# REB215_XPRO_A_RF.net
KiCad netlist of a schematic drawn in Altium Designer
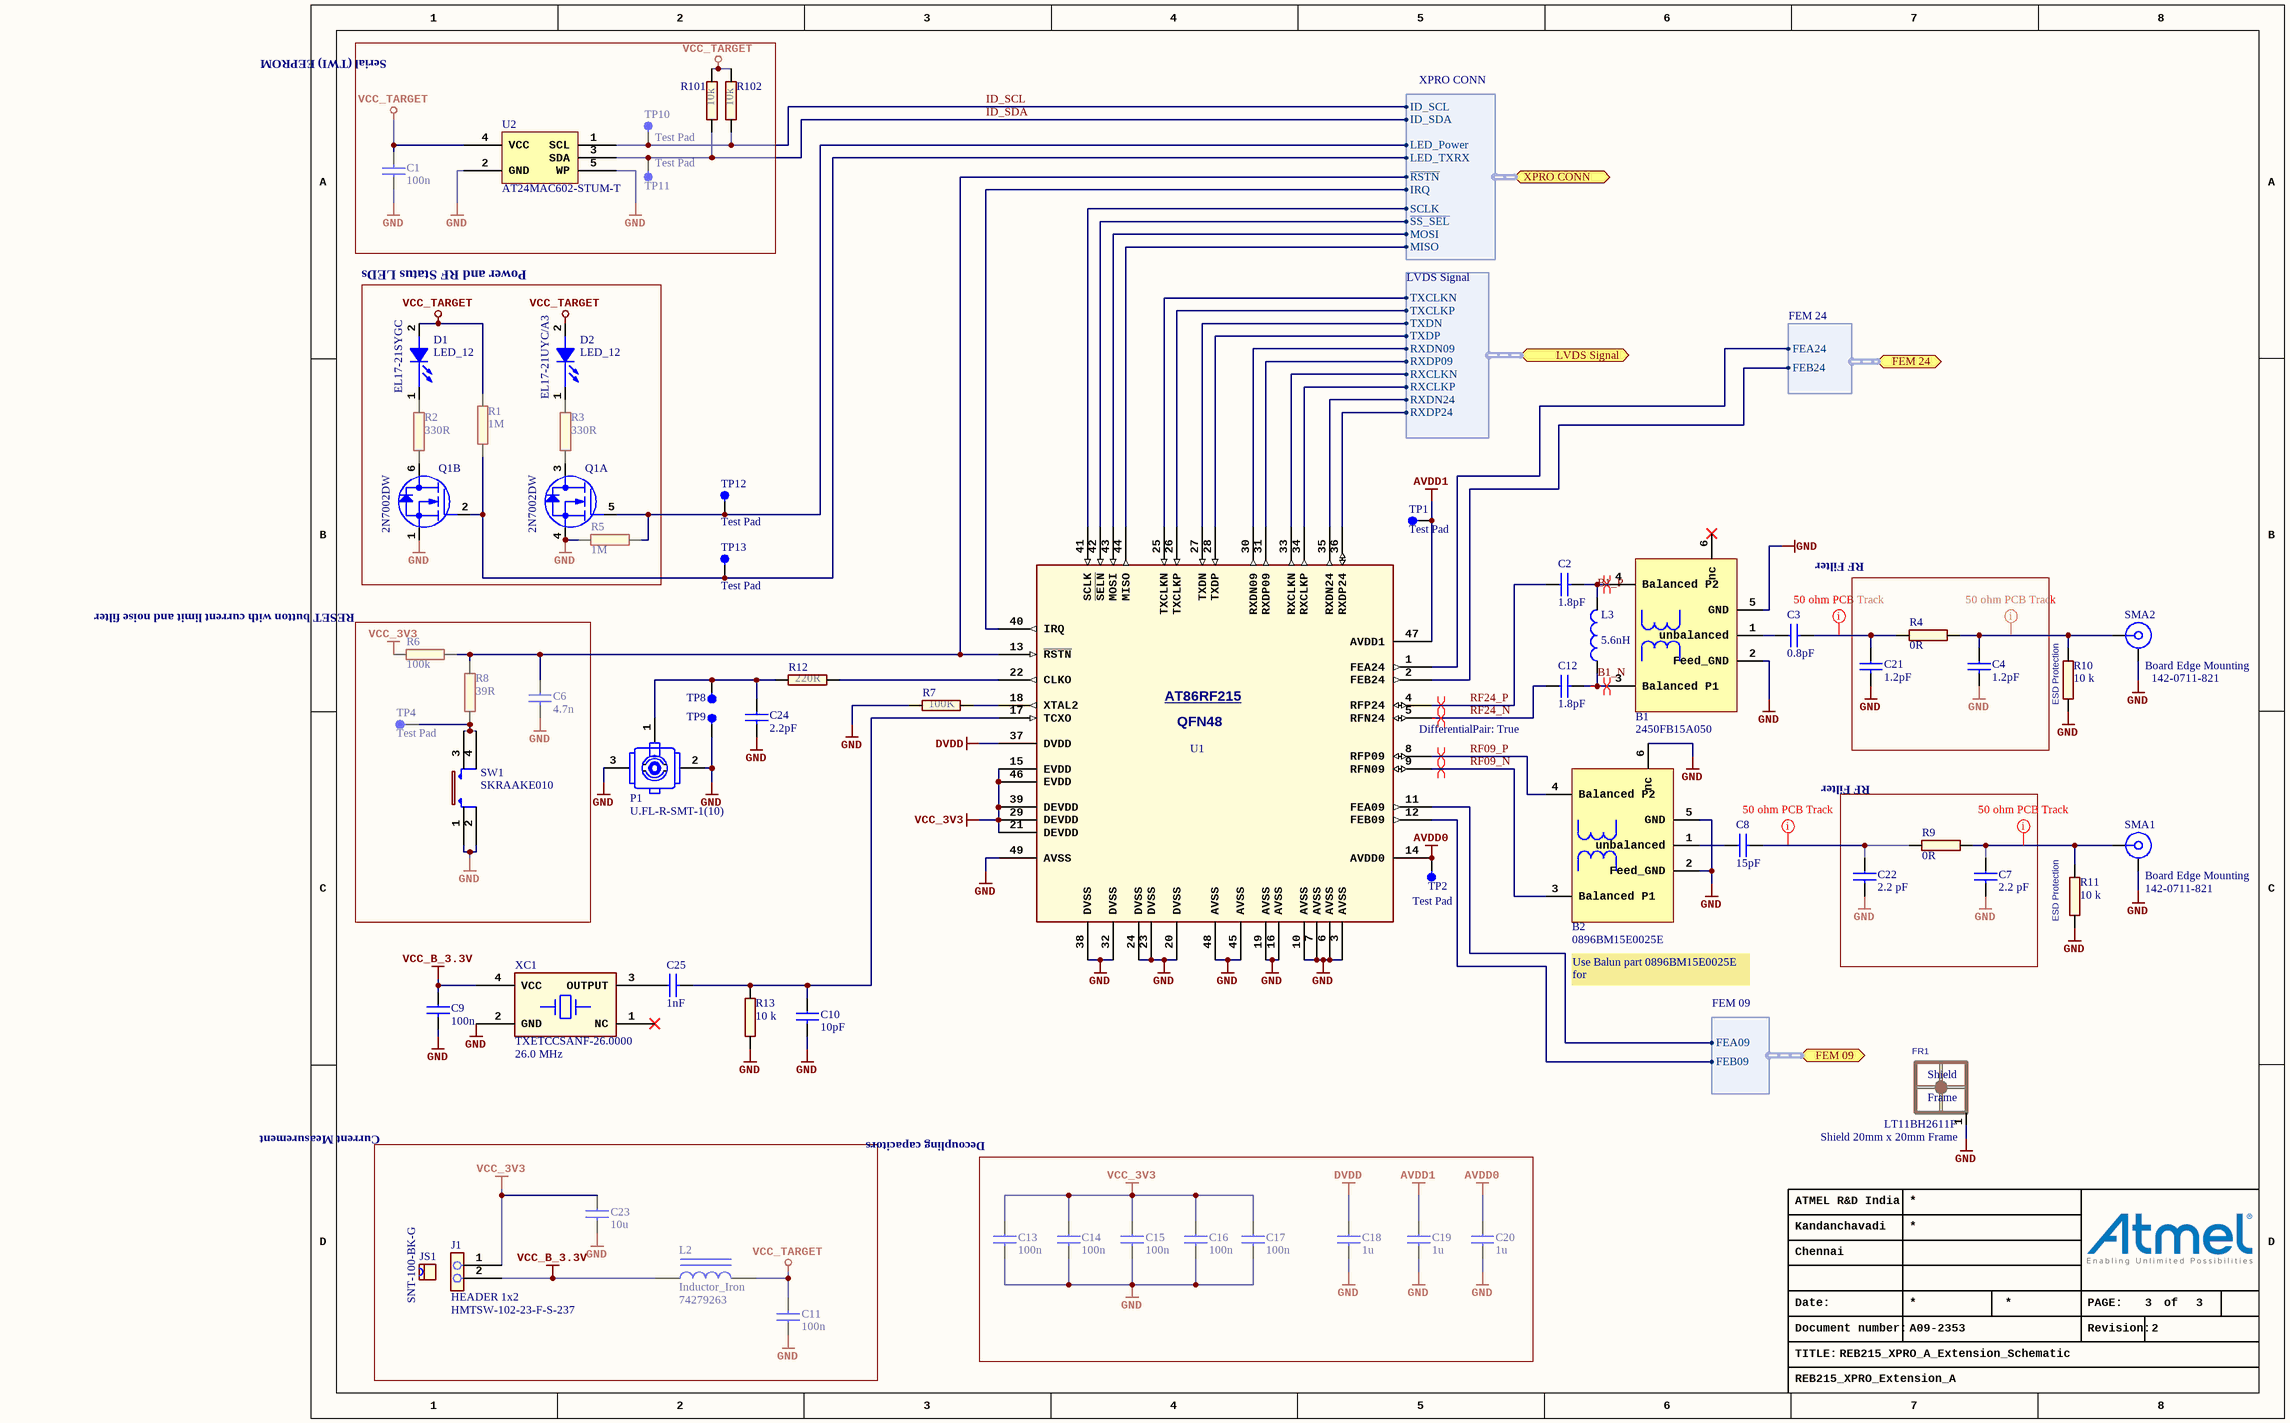
[diagram p0: REB215_XPRO_A_RF.SchDoc]

(export (version "E")
  (design (tool "Eeschema 10.0.6"))
  (components
    (comp (ref "B1")
      (value "2450FB15A050")
      (footprint "AP3-00060")
      (description "2.45 GHz Balun / Filter Combination")
      (fields (field (name "MANUFACTURER") "Johanson Technology") (field (name "Comment") "Balun_2.4GHz"))
      (libsource (lib "AltiumDbLib") (part "Balun_2.4GHz"))
    )
    (comp (ref "B2")
      (value "0896BM15E0025E")
      (footprint "AP3-00060")
      (description "863/915 MHz ISM band Balun+LPF for AT86RF215")
      (fields (field (name "MANUFACTURER") "Johanson Technology") (field (name "Comment") "Balun_2.4GHz"))
      (libsource (lib "AltiumDbLib") (part "Balun_2.4GHz"))
    )
    (comp (ref "C1")
      (value "100n")
      (footprint "AP1-00001")
      (description "Ceramic capacitor, SMD 0402, X7R, 16V, +/-10%")
      (fields
        (field (name "TOLERANCE") "16V, +/-10%")
        (field (name "MANUFACTURER") "Kemet")
        (field (name "VERIFIED BY") "Lars Helge Mo")
      )
      (libsource (lib "AltiumDbLib") (part "CAP-NONPOL"))
    )
    (comp (ref "C2")
      (value "1.8pF")
      (footprint "AP1-00035")
      (description "CAP CER 1.8PF 25V NP0 0201")
      (fields
        (field (name "TOLERANCE") "Â±0.1pF")
        (field (name "MANUFACTURER") "Johanson Technology")
        (field (name "VERIFIED BY") "Lars Helge Mo")
      )
      (libsource (lib "AltiumDbLib") (part "CAP-NONPOL"))
    )
    (comp (ref "C3")
      (value "0.8pF")
      (footprint "AP1-00035")
      (description "CAP CER 0.8PF 25V NP0 0201")
      (fields
        (field (name "TOLERANCE") "Â±0.05pF")
        (field (name "MANUFACTURER") "Johanson Technology")
        (field (name "VERIFIED BY") "Lars Helge Mo")
      )
      (libsource (lib "AltiumDbLib") (part "CAP-NONPOL"))
    )
    (comp (ref "C4")
      (value "1.2pF")
      (footprint "AP1-00035")
      (description "Ceramic Capacitor, SMD 0201, 25V, NP0, 1.2pF")
      (fields
        (field (name "MANUFACTURER") "Johanson Technology")
        (field (name "MPN") "250R05L1R2CV4T")
        (field (name "VERIFIED BY") "Lars Helge Mo")
      )
      (libsource (lib "AltiumDbLib") (part "CAP-NONPOL"))
    )
    (comp (ref "C6")
      (value "4.7n")
      (footprint "AP1-00001")
      (description "Ceramic capacitor, SMD 0402, X7R, 25V, +/-10% (de35287)")
      (fields
        (field (name "TOLERANCE") "25V, +/-10%")
        (field (name "Comment") "CAP-NONPOL")
        (field (name "VERIFIED BY") "Lars Helge Mo")
      )
      (libsource (lib "AltiumDbLib") (part "CAP-NONPOL"))
    )
    (comp (ref "C7")
      (value "2.2 pF")
      (footprint "AP1-00032")
      (description "CAP CER 2.2PF 6.3V NP0 0201")
      (fields
        (field (name "TOLERANCE") "±0.25pF")
        (field (name "MANUFACTURER") "Kemet")
        (field (name "VERIFIED BY") "Lars Helge Mo")
      )
      (libsource (lib "AltiumDbLib") (part "CAP-NONPOL"))
    )
    (comp (ref "C8")
      (value "15pF")
      (footprint "AP1-00032")
      (description "CAP CER 15PF 25V NP0 0201")
      (fields
        (field (name "TOLERANCE") "Â±5%")
        (field (name "MANUFACTURER") "Murata")
        (field (name "VERIFIED BY") "Lars Helge Mo")
      )
      (libsource (lib "AltiumDbLib") (part "CAP-NONPOL"))
    )
    (comp (ref "C9")
      (value "100n")
      (footprint "AP1-00001")
      (description "Ceramic capacitor, SMD 0402, X7R, 16V, +/-10%")
      (fields
        (field (name "TOLERANCE") "16V, +/-10%")
        (field (name "MANUFACTURER") "Kemet")
        (field (name "VERIFIED BY") "Lars Helge Mo")
      )
      (libsource (lib "AltiumDbLib") (part "CAP-NONPOL"))
    )
    (comp (ref "C10")
      (value "10pF")
      (footprint "AP1-00032")
      (description "CAP CER 10PF 25V Â±.25pf ( and Â±.30ppm/ degree C of temp variation) NP0 0201")
      (fields
        (field (name "TOLERANCE") "Â±20ppm to Â±50ppm")
        (field (name "MANUFACTURER") "tdk")
        (field (name "VERIFIED BY") "Lars Helge Mo")
      )
      (libsource (lib "AltiumDbLib") (part "CAP-NONPOL"))
    )
    (comp (ref "C11")
      (value "100n")
      (footprint "AP1-00001")
      (description "Ceramic capacitor, SMD 0402, X7R, 16V, +/-10%")
      (fields
        (field (name "TOLERANCE") "16V, +/-10%")
        (field (name "MANUFACTURER") "Kemet")
        (field (name "VERIFIED BY") "Lars Helge Mo")
      )
      (libsource (lib "AltiumDbLib") (part "CAP-NONPOL"))
    )
    (comp (ref "C12")
      (value "1.8pF")
      (footprint "AP1-00035")
      (description "CAP CER 1.8PF 25V NP0 0201")
      (fields
        (field (name "TOLERANCE") "Â±0.1pF")
        (field (name "MANUFACTURER") "Johanson Technology")
        (field (name "VERIFIED BY") "Lars Helge Mo")
      )
      (libsource (lib "AltiumDbLib") (part "CAP-NONPOL"))
    )
    (comp (ref "C13")
      (value "100n")
      (footprint "AP1-00001")
      (description "Ceramic capacitor, SMD 0402, X7R, 16V, +/-10%")
      (fields
        (field (name "TOLERANCE") "16V, +/-10%")
        (field (name "MANUFACTURER") "Kemet")
        (field (name "VERIFIED BY") "Lars Helge Mo")
      )
      (libsource (lib "AltiumDbLib") (part "CAP-NONPOL"))
    )
    (comp (ref "C14")
      (value "100n")
      (footprint "AP1-00001")
      (description "Ceramic capacitor, SMD 0402, X7R, 16V, +/-10%")
      (fields
        (field (name "TOLERANCE") "16V, +/-10%")
        (field (name "MANUFACTURER") "Kemet")
        (field (name "VERIFIED BY") "Lars Helge Mo")
      )
      (libsource (lib "AltiumDbLib") (part "CAP-NONPOL"))
    )
    (comp (ref "C15")
      (value "100n")
      (footprint "AP1-00001")
      (description "Ceramic capacitor, SMD 0402, X7R, 16V, +/-10%")
      (fields
        (field (name "TOLERANCE") "16V, +/-10%")
        (field (name "MANUFACTURER") "Kemet")
        (field (name "VERIFIED BY") "Lars Helge Mo")
      )
      (libsource (lib "AltiumDbLib") (part "CAP-NONPOL"))
    )
    (comp (ref "C16")
      (value "100n")
      (footprint "AP1-00001")
      (description "Ceramic capacitor, SMD 0402, X7R, 16V, +/-10%")
      (fields
        (field (name "TOLERANCE") "16V, +/-10%")
        (field (name "MANUFACTURER") "Kemet")
        (field (name "VERIFIED BY") "Lars Helge Mo")
      )
      (libsource (lib "AltiumDbLib") (part "CAP-NONPOL"))
    )
    (comp (ref "C17")
      (value "100n")
      (footprint "AP1-00001")
      (description "Ceramic capacitor, SMD 0402, X7R, 16V, +/-10%")
      (fields
        (field (name "TOLERANCE") "16V, +/-10%")
        (field (name "MANUFACTURER") "Kemet")
        (field (name "VERIFIED BY") "Lars Helge Mo")
      )
      (libsource (lib "AltiumDbLib") (part "CAP-NONPOL"))
    )
    (comp (ref "C18")
      (value "1u")
      (footprint "AP1-00001")
      (description "Ceramic capacitor, SMD 0402, X5R, 6.3V, +/-10% (de26942)")
      (fields
        (field (name "TOLERANCE") "+/-10%")
        (field (name "MANUFACTURER") "Kemet")
        (field (name "VERIFIED BY") "Lars Helge Mo")
      )
      (libsource (lib "AltiumDbLib") (part "CAP-NONPOL"))
    )
    (comp (ref "C19")
      (value "1u")
      (footprint "AP1-00001")
      (description "Ceramic capacitor, SMD 0402, X5R, 6.3V, +/-10% (de26942)")
      (fields
        (field (name "TOLERANCE") "+/-10%")
        (field (name "MANUFACTURER") "Kemet")
        (field (name "VERIFIED BY") "Lars Helge Mo")
      )
      (libsource (lib "AltiumDbLib") (part "CAP-NONPOL"))
    )
    (comp (ref "C20")
      (value "1u")
      (footprint "AP1-00001")
      (description "Ceramic capacitor, SMD 0402, X5R, 6.3V, +/-10% (de26942)")
      (fields
        (field (name "TOLERANCE") "+/-10%")
        (field (name "MANUFACTURER") "Kemet")
        (field (name "VERIFIED BY") "Lars Helge Mo")
      )
      (libsource (lib "AltiumDbLib") (part "CAP-NONPOL"))
    )
    (comp (ref "C21")
      (value "1.2pF")
      (footprint "AP1-00035")
      (description "Ceramic Capacitor, SMD 0201, 25V, NP0, 1.2pF")
      (fields
        (field (name "MANUFACTURER") "Johanson Technology")
        (field (name "MPN") "250R05L1R2CV4T")
        (field (name "VERIFIED BY") "Lars Helge Mo")
      )
      (libsource (lib "AltiumDbLib") (part "CAP-NONPOL"))
    )
    (comp (ref "C22")
      (value "2.2 pF")
      (footprint "AP1-00032")
      (description "CAP CER 2.2PF 6.3V NP0 0201")
      (fields
        (field (name "TOLERANCE") "±0.25pF")
        (field (name "MANUFACTURER") "Kemet")
        (field (name "VERIFIED BY") "Lars Helge Mo")
      )
      (libsource (lib "AltiumDbLib") (part "CAP-NONPOL"))
    )
    (comp (ref "C23")
      (value "10u")
      (footprint "AP1-00026")
      (description "Ceramic capacitor, SMD 1206, X5R, 6.3V, ±10%")
      (fields
        (field (name "TOLERANCE") "±10%")
        (field (name "MANUFACTURER") "Murata")
        (field (name "VERIFIED BY") "Lars Helge Mo")
      )
      (libsource (lib "AltiumDbLib") (part "CAP-NONPOL"))
    )
    (comp (ref "C24")
      (value "2.2pF")
      (footprint "AP1-00038")
      (description "Ceramic capacitor, SMD 0402, NP0, 50V, +/-0.25pF (de23847)")
      (fields
        (field (name "TOLERANCE") "0,25pF")
        (field (name "MANUFACTURER") "Murata")
        (field (name "VERIFIED BY") "Lars Helge Mo")
      )
      (libsource (lib "AltiumDbLib") (part "CAP-NONPOL"))
    )
    (comp (ref "C25")
      (value "1nF")
      (footprint "AP1-00035")
      (description "Ceramic capacitor, SMD 0201, X7R, 10V, +/-10%")
      (fields
        (field (name "MANUFACTURER") "Johanson Technology")
        (field (name "MPN") "100R05W102KV4")
        (field (name "VERIFIED BY") "Lars Helge Mo")
      )
      (libsource (lib "AltiumDbLib") (part "CAP-NONPOL"))
    )
    (comp (ref "D1")
      (value "LED_12")
      (footprint "AP4-00013")
      (description "LED, Green, Wave length=575nm, SMD 0805, ±70°")
      (fields
        (field (name "ALTIUM_VALUE") "EL17-21SYGC")
        (field (name "MANUFACTURER") "Everlight")
        (field (name "MPN") "EL17-21SYGC")
        (field (name "VERIFIED BY") "Sveinung Helgeland")
      )
      (libsource (lib "AltiumDbLib") (part "LED_12"))
    )
    (comp (ref "D2")
      (value "LED_12")
      (footprint "AP4-00013")
      (description "LED, Yellow, Wave length=591nm, SMD 0805, ±70°")
      (fields
        (field (name "ALTIUM_VALUE") "EL17-21UYC/A3")
        (field (name "MANUFACTURER") "Everlight")
        (field (name "MPN") "17-21UYC/S530-A3/TR8")
        (field (name "VERIFIED BY") "Sveinung Helgeland")
      )
      (libsource (lib "AltiumDbLib") (part "LED_12"))
    )
    (comp (ref "FR1")
      (value "Shield 20mm x 20mm Frame")
      (footprint "AP8-00753")
      (description "SMD frame for metal shield 20mm x 20mm (de34031)")
      (fields
        (field (name "ALTIUM_VALUE") "LT11BH2611F")
        (field (name "MANUFACTURER") "Laird Technologies")
        (field (name "MPN") "LT11BH2611F")
      )
      (libsource (lib "AltiumDbLib") (part "FRAME20X20MM"))
    )
    (comp (ref "J1")
      (value "HEADER 1x2")
      (footprint "AP8-00733")
      (description "1x2 pin header, 2.54mm pitch, Pin-in-Paste THM")
      (fields
        (field (name "ALTIUM_VALUE") "HMTSW-102-23-F-S-237")
        (field (name "MANUFACTURER") "SAMTEC")
        (field (name "MPN") "HMTSW-102-23-F-S-237")
        (field (name "VERIFIED BY") "Lars Helge")
      )
      (libsource (lib "AltiumDbLib") (part "HEADER 1x2"))
    )
    (comp (ref "JS1")
      (value "SNT-100-BK-G")
      (footprint "AP8-00525")
      (description "Jumper cap for 2.54mm pinheader")
      (fields
        (field (name "MANUFACTURER") "SAMTEC")
        (field (name "Comment") "To be used by request from ESCATEC")
        (field (name "VERIFIED BY") "Lars Helge Mo")
      )
      (libsource (lib "AltiumDbLib") (part "JUMPER_CAP"))
    )
    (comp (ref "L2")
      (value "Inductor_Iron")
      (footprint "AP3-00049")
      (description "SMD-Ferrite 220Ohm, 100MHz 0603 size, (de14411)")
      (fields
        (field (name "ALTIUM_VALUE") "74279263")
        (field (name "MANUFACTURER") "Wurth Elektronik")
        (field (name "MPN") "74279263")
      )
      (libsource (lib "AltiumDbLib") (part "Inductor_Iron"))
    )
    (comp (ref "L3")
      (value "5.6nH")
      (footprint "AP3-00041")
      (description "ceramic chip inductor, 5.6nH, 0201")
      (fields
        (field (name "TOLERANCE") "±0.3nH")
        (field (name "MANUFACTURER") "Johanson Technology")
        (field (name "VERIFIED BY") "Lars Helge Mo")
      )
      (libsource (lib "AltiumDbLib") (part "INDUCTOR"))
    )
    (comp (ref "P1")
      (value "U.FL-R-SMT-1(10)")
      (footprint "AP8-00380")
      (description "UFL (Small Coax Connector)")
      (fields (field (name "MANUFACTURER") "HIROSE") (field (name "Comment") "Copy of A08-0629"))
      (libsource (lib "AltiumDbLib") (part "U.FL-R-SMT"))
    )
    (comp (ref "Q1")
      (value "2N7002DW")
      (footprint "AP5-00001")
      (description "Dual N-Channel MOSFET, 60V, 115mA cont,RDS(ON) < 7.5 Ohm @50mA@5V, SOT-363")
      (fields
        (field (name "MANUFACTURER") "Fairchild")
        (field (name "Comment") "Same as 2N7002 but with two MOSFETs in one package")
      )
      (libsource (lib "AltiumDbLib") (part "MOSFET_DUAL_N_S2G2D1S1G1D2"))
    )
    (comp (ref "R1")
      (value "1M")
      (footprint "AP2-00000")
      (description "Thick film resistor, SMD 0402, 1/16W, 1%")
      (fields
        (field (name "TOLERANCE") "1 %")
        (field (name "Comment") "R2")
        (field (name "VERIFIED BY") "Lars Helge Mo")
      )
      (libsource (lib "") (part "R2_1"))
    )
    (comp (ref "R2")
      (value "330R")
      (footprint "AP2-00000")
      (description "Thick film resistor, SMD 0402, 1/16W, 1%")
      (fields
        (field (name "TOLERANCE") "1 %")
        (field (name "Comment") "R2")
        (field (name "VERIFIED BY") "Lars Helge Mo")
      )
      (libsource (lib "") (part "R2_1"))
    )
    (comp (ref "R3")
      (value "330R")
      (footprint "AP2-00000")
      (description "Thick film resistor, SMD 0402, 1/16W, 1%")
      (fields
        (field (name "TOLERANCE") "1 %")
        (field (name "Comment") "R2")
        (field (name "VERIFIED BY") "Lars Helge Mo")
      )
      (libsource (lib "") (part "R2_1"))
    )
    (comp (ref "R4")
      (value "0R")
      (footprint "AP2-00028")
      (description "Thick film resistor, SMD 0201, 1/20W, 5%")
      (fields
        (field (name "TOLERANCE") "5%")
        (field (name "MANUFACTURER") "ROHM")
        (field (name "VERIFIED BY") "Lars Helge Mo")
      )
      (libsource (lib "") (part "R2_2"))
    )
    (comp (ref "R5")
      (value "1M")
      (footprint "AP2-00000")
      (description "Thick film resistor, SMD 0402, 1/16W, 1%")
      (fields
        (field (name "TOLERANCE") "1 %")
        (field (name "Comment") "R2")
        (field (name "VERIFIED BY") "Lars Helge Mo")
      )
      (libsource (lib "AltiumDbLib") (part "R2"))
    )
    (comp (ref "R6")
      (value "100k")
      (footprint "AP2-00000")
      (description "Thick film resistor, SMD 0402, 1/16W, 1%")
      (fields
        (field (name "TOLERANCE") "1 %")
        (field (name "Comment") "R2")
        (field (name "VERIFIED BY") "Lars Helge Mo")
      )
      (libsource (lib "AltiumDbLib") (part "R2"))
    )
    (comp (ref "R7")
      (value "100K")
      (footprint "AP2-00028")
      (description "RES 100K OHM 1/20W 5% 0201 SMD")
      (fields
        (field (name "MANUFACTURER") "YAGEO CORP")
        (field (name "MPN") "RC0201JR-07100KL")
        (field (name "VERIFIED BY") "Lars Helge Mo")
      )
      (libsource (lib "AltiumDbLib") (part "R2"))
    )
    (comp (ref "R8")
      (value "39R")
      (footprint "AP2-00000")
      (description "Thick film resistor, SMD 0402, 1/16W, 1%")
      (fields
        (field (name "TOLERANCE") "1 %")
        (field (name "Comment") "R2")
        (field (name "VERIFIED BY") "Lars Helge Mo")
      )
      (libsource (lib "") (part "R2_1"))
    )
    (comp (ref "R9")
      (value "0R")
      (footprint "AP2-00028")
      (description "Thick film resistor, SMD 0201, 1/20W, 5%")
      (fields
        (field (name "TOLERANCE") "5%")
        (field (name "MANUFACTURER") "ROHM")
        (field (name "VERIFIED BY") "Lars Helge Mo")
      )
      (libsource (lib "") (part "R2_2"))
    )
    (comp (ref "R10")
      (value "10 k")
      (footprint "AP2-00028")
      (description "Thick film resistor, SMD 0201, 1/20W, 5%")
      (fields
        (field (name "TOLERANCE") "5%")
        (field (name "MANUFACTURER") "ROHM")
        (field (name "VERIFIED BY") "Lars Helge Mo")
      )
      (libsource (lib "") (part "R2_1"))
    )
    (comp (ref "R11")
      (value "10 k")
      (footprint "AP2-00028")
      (description "Thick film resistor, SMD 0201, 1/20W, 5%")
      (fields
        (field (name "TOLERANCE") "5%")
        (field (name "MANUFACTURER") "ROHM")
        (field (name "VERIFIED BY") "Lars Helge Mo")
      )
      (libsource (lib "") (part "R2_1"))
    )
    (comp (ref "R12")
      (value "220R")
      (footprint "AP2-00000")
      (description "Thick film resistor, SMD 0402, 1/16W, 1%")
      (fields
        (field (name "TOLERANCE") "1 %")
        (field (name "Comment") "R2")
        (field (name "VERIFIED BY") "Lars Helge Mo")
      )
      (libsource (lib "") (part "R2_2"))
    )
    (comp (ref "R13")
      (value "10 k")
      (footprint "AP2-00028")
      (description "Thick film resistor, SMD 0201, 1/20W, 5%")
      (fields
        (field (name "TOLERANCE") "5%")
        (field (name "MANUFACTURER") "ROHM")
        (field (name "VERIFIED BY") "Lars Helge Mo")
      )
      (libsource (lib "") (part "R2_1"))
    )
    (comp (ref "R101")
      (value "10k")
      (footprint "AP2-00000")
      (description "Thick film resistor, SMD 0402, 1/16W, 1%")
      (fields
        (field (name "TOLERANCE") "1 %")
        (field (name "MANUFACTURER") "vishay")
        (field (name "VERIFIED BY") "Lars Helge Mo")
      )
      (libsource (lib "") (part "R2_1"))
    )
    (comp (ref "R102")
      (value "10k")
      (footprint "AP2-00000")
      (description "Thick film resistor, SMD 0402, 1/16W, 1%")
      (fields
        (field (name "TOLERANCE") "1 %")
        (field (name "MANUFACTURER") "vishay")
        (field (name "VERIFIED BY") "Lars Helge Mo")
      )
      (libsource (lib "") (part "R2_1"))
    )
    (comp (ref "SMA1")
      (value "Board Edge Mounting")
      (footprint "AP8-00443")
      (description "End Launch Jack Receptacle, Round Contact (de21535)")
      (fields
        (field (name "ALTIUM_VALUE") "142-0711-821")
        (field (name "MANUFACTURER") "EMERSON")
        (field (name "MPN") "142-0711-821")
      )
      (libsource (lib "AltiumDbLib") (part "SMA_3_pin"))
    )
    (comp (ref "SMA2")
      (value "Board Edge Mounting")
      (footprint "AP8-00443")
      (description "End Launch Jack Receptacle, Round Contact (de21535)")
      (fields
        (field (name "ALTIUM_VALUE") "142-0711-821")
        (field (name "MANUFACTURER") "EMERSON")
        (field (name "MPN") "142-0711-821")
      )
      (libsource (lib "AltiumDbLib") (part "SMA_3_pin"))
    )
    (comp (ref "SW1")
      (value "SKRAAKE010")
      (footprint "AP8-00137")
      (description "SWITCH, SMD, 2.45N, 6.2mm X 6.2mm")
      (fields
        (field (name "MANUFACTURER") "ALPS")
        (field (name "Comment") "same as A08-0091 but less force is needed; Can be ordered in low volumes from Mouser")
        (field (name "VERIFIED BY") "Ketil Skjerve")
      )
      (libsource (lib "AltiumDbLib") (part "PUSHBUTTON1"))
    )
    (comp (ref "TP1")
      (value "Test Pad")
      (footprint "AP8-00399")
      (description "Single SMD testpad")
      (fields (field (name "Comment") "TESTPOINT") (field (name "VERIFIED BY") "Sveinung Helgeland"))
      (libsource (lib "AltiumDbLib") (part "TESTPOINT"))
    )
    (comp (ref "TP2")
      (value "Test Pad")
      (footprint "AP8-00399")
      (description "Single SMD testpad")
      (fields (field (name "Comment") "TESTPOINT") (field (name "VERIFIED BY") "Sveinung Helgeland"))
      (libsource (lib "AltiumDbLib") (part "TESTPOINT"))
    )
    (comp (ref "TP4")
      (value "Test Pad")
      (footprint "AP8-00399")
      (description "Single SMD testpad")
      (fields (field (name "Comment") "TESTPOINT") (field (name "VERIFIED BY") "Sveinung Helgeland"))
      (libsource (lib "AltiumDbLib") (part "TESTPOINT"))
    )
    (comp (ref "TP8")
      (value "Mounting hole dia should be 1.6mm. Refer A08-2059")
      (footprint "AP8-00710")
      (description "THM Test Point, Without Base, 1.0mm Dia. Mounting")
      (fields
        (field (name "MANUFACTURER") "Keystone Corp.")
        (field (name "MPN") "5012")
        (field (name "VERIFIED BY") "Sveinung Helgeland")
      )
      (libsource (lib "AltiumDbLib") (part "TESTPOINT"))
    )
    (comp (ref "TP9")
      (value "Mounting hole dia should be 1.6mm. Refer A08-2059")
      (footprint "AP8-00710")
      (description "THM Test Point, Without Base, 1.0mm Dia. Mounting")
      (fields
        (field (name "MANUFACTURER") "Keystone Corp.")
        (field (name "MPN") "5012")
        (field (name "VERIFIED BY") "Sveinung Helgeland")
      )
      (libsource (lib "AltiumDbLib") (part "TESTPOINT"))
    )
    (comp (ref "TP10")
      (value "Test Pad")
      (footprint "AP8-00399")
      (description "Single SMD testpad")
      (fields (field (name "Comment") "TESTPOINT") (field (name "VERIFIED BY") "Sveinung Helgeland"))
      (libsource (lib "AltiumDbLib") (part "TESTPOINT"))
    )
    (comp (ref "TP11")
      (value "Test Pad")
      (footprint "AP8-00399")
      (description "Single SMD testpad")
      (fields (field (name "Comment") "TESTPOINT") (field (name "VERIFIED BY") "Sveinung Helgeland"))
      (libsource (lib "AltiumDbLib") (part "TESTPOINT"))
    )
    (comp (ref "TP12")
      (value "Test Pad")
      (footprint "AP8-00399")
      (description "Single SMD testpad")
      (fields (field (name "Comment") "TESTPOINT") (field (name "VERIFIED BY") "Sveinung Helgeland"))
      (libsource (lib "AltiumDbLib") (part "TESTPOINT"))
    )
    (comp (ref "TP13")
      (value "Test Pad")
      (footprint "AP8-00399")
      (description "Single SMD testpad")
      (fields (field (name "Comment") "TESTPOINT") (field (name "VERIFIED BY") "Sveinung Helgeland"))
      (libsource (lib "AltiumDbLib") (part "TESTPOINT"))
    )
    (comp (ref "U1")
      (value "48 lead QFN package")
      (footprint "AP6-00345")
      (description "Sub-1GHz/2.4GHz Transceiver")
      (fields (field (name "MANUFACTURER") "ATMEL") (field (name "MPN") "AT86RF215-ZU"))
      (libsource (lib "AltiumDbLib") (part "AT86RF215"))
    )
    (comp (ref "U2")
      (value "AT24MAC602-STUM-T")
      (footprint "AP6-00014")
      (description "IC EEPROM 2KBIT 1MHz, 1.7V to 5.5V, SOT23-5")
      (fields
        (field (name "MANUFACTURER") "ATMEL")
        (field (name "Comment") "AT24MAC602")
        (field (name "VERIFIED BY") "*")
      )
      (libsource (lib "AltiumDbLib") (part "AT24MAC602"))
    )
    (comp (ref "XC1")
      (value "TXETCCSANF-26.0000")
      (footprint "AP7-00060")
      (description "26MHz TCXO, 2.8 ~ 3.3V, Clipped sine wave 10KOhm/10pF, 3.2 x 2.5 mm SMD")
      (fields
        (field (name "ALTIUM_VALUE") "26.0 MHz")
        (field (name "TOLERANCE") "+/-2ppm")
        (field (name "MANUFACTURER") "Taiway Electronics")
      )
      (libsource (lib "AltiumDbLib") (part "ACT33T-4 TCXO"))
    )
  )
  (nets
    (net (code "8") (name "/B1_N") (class "Default")
      (node (ref "B1") (pin "3") (pinfunction "Balanced_P1_3") (pintype "passive"))
      (node (ref "C12") (pin "2") (pinfunction "2_2") (pintype "passive"))
      (node (ref "L3") (pin "1") (pinfunction "1_1") (pintype "passive"))
    )
    (net (code "9") (name "/B1_P") (class "Default")
      (node (ref "B1") (pin "4") (pinfunction "Balanced_P2_4") (pintype "passive"))
      (node (ref "C2") (pin "2") (pinfunction "2_2") (pintype "passive"))
      (node (ref "L3") (pin "2") (pinfunction "2_2") (pintype "passive"))
    )
    (net (code "10") (name "/FEA09") (class "Default")
      (node (ref "U1") (pin "11") (pinfunction "FEA09_11") (pintype "output"))
    )
    (net (code "11") (name "/FEA24") (class "Default")
      (node (ref "U1") (pin "1") (pinfunction "FEA24_1") (pintype "output"))
    )
    (net (code "12") (name "/FEB09") (class "Default")
      (node (ref "U1") (pin "12") (pinfunction "FEB09_12") (pintype "output"))
    )
    (net (code "13") (name "/FEB24") (class "Default")
      (node (ref "U1") (pin "2") (pinfunction "FEB24_2") (pintype "output"))
    )
    (net (code "14") (name "/ID_SCL") (class "Default")
      (node (ref "R102") (pin "1") (pinfunction "1_1") (pintype "passive"))
      (node (ref "TP10") (pin "1") (pinfunction "1_1") (pintype "passive"))
      (node (ref "U2") (pin "1") (pinfunction "SCL_1") (pintype "passive"))
    )
    (net (code "15") (name "/ID_SDA") (class "Default")
      (node (ref "R101") (pin "1") (pinfunction "1_1") (pintype "passive"))
      (node (ref "TP11") (pin "1") (pinfunction "1_1") (pintype "passive"))
      (node (ref "U2") (pin "3") (pinfunction "SDA_3") (pintype "passive"))
    )
    (net (code "16") (name "/IRQ") (class "Default")
      (node (ref "U1") (pin "40") (pinfunction "IRQ_40") (pintype "output"))
    )
    (net (code "17") (name "/LED_Power") (class "Default")
      (node (ref "Q1") (pin "5") (pinfunction "G1_5") (pintype "passive"))
      (node (ref "R5") (pin "1") (pinfunction "1_1") (pintype "passive"))
      (node (ref "TP12") (pin "1") (pinfunction "1_1") (pintype "passive"))
    )
    (net (code "18") (name "/LED_TXRX") (class "Default")
      (node (ref "Q1") (pin "2") (pinfunction "G2_2") (pintype "passive"))
      (node (ref "R1") (pin "1") (pinfunction "1_1") (pintype "passive"))
      (node (ref "TP13") (pin "1") (pinfunction "1_1") (pintype "passive"))
    )
    (net (code "19") (name "/MISO") (class "Default")
      (node (ref "U1") (pin "44") (pinfunction "MISO_44") (pintype "output"))
    )
    (net (code "20") (name "/MOSI") (class "Default")
      (node (ref "U1") (pin "43") (pinfunction "MOSI_43") (pintype "input"))
    )
    (net (code "21") (name "/RF09_N") (class "Default")
      (node (ref "B2") (pin "3") (pinfunction "Balanced_P1_3") (pintype "passive"))
      (node (ref "U1") (pin "9") (pinfunction "RFN09_9") (pintype "bidirectional"))
    )
    (net (code "22") (name "/RF09_P") (class "Default")
      (node (ref "B2") (pin "4") (pinfunction "Balanced_P2_4") (pintype "passive"))
      (node (ref "U1") (pin "8") (pinfunction "RFP09_8") (pintype "bidirectional"))
    )
    (net (code "23") (name "/RF24_N") (class "Default")
      (node (ref "C12") (pin "1") (pinfunction "1_1") (pintype "passive"))
      (node (ref "U1") (pin "5") (pinfunction "RFN24_5") (pintype "bidirectional"))
    )
    (net (code "24") (name "/RF24_P") (class "Default")
      (node (ref "C2") (pin "1") (pinfunction "1_1") (pintype "passive"))
      (node (ref "U1") (pin "4") (pinfunction "RFP24_4") (pintype "bidirectional"))
    )
    (net (code "25") (name "/RXCLKN") (class "Default")
      (node (ref "U1") (pin "33") (pinfunction "RXCLKN_33") (pintype "output"))
    )
    (net (code "26") (name "/RXCLKP") (class "Default")
      (node (ref "U1") (pin "34") (pinfunction "RXCLKP_34") (pintype "output"))
    )
    (net (code "27") (name "/RXDN09") (class "Default")
      (node (ref "U1") (pin "30") (pinfunction "RXDN09_30") (pintype "output"))
    )
    (net (code "28") (name "/RXDN24") (class "Default")
      (node (ref "U1") (pin "35") (pinfunction "RXDN24_35") (pintype "output"))
    )
    (net (code "29") (name "/RXDP09") (class "Default")
      (node (ref "U1") (pin "31") (pinfunction "RXDP09_31") (pintype "output"))
    )
    (net (code "30") (name "/RXDP24") (class "Default")
      (node (ref "U1") (pin "36") (pinfunction "RXDP24_36") (pintype "bidirectional"))
    )
    (net (code "31") (name "/SCLK") (class "Default")
      (node (ref "U1") (pin "41") (pinfunction "SCLK_41") (pintype "input"))
    )
    (net (code "32") (name "/TXCLKN") (class "Default")
      (node (ref "U1") (pin "25") (pinfunction "TXCLKN_25") (pintype "input"))
    )
    (net (code "33") (name "/TXCLKP") (class "Default")
      (node (ref "U1") (pin "26") (pinfunction "TXCLKP_26") (pintype "input"))
    )
    (net (code "34") (name "/TXDN") (class "Default")
      (node (ref "U1") (pin "27") (pinfunction "TXDN_27") (pintype "input"))
    )
    (net (code "35") (name "/TXDP") (class "Default")
      (node (ref "U1") (pin "28") (pinfunction "TXDP_28") (pintype "input"))
    )
    (net (code "40") (name "/~{RSTN}") (class "Default")
      (node (ref "C6") (pin "1") (pinfunction "1_1") (pintype "passive"))
      (node (ref "R6") (pin "1") (pinfunction "1_1") (pintype "passive"))
      (node (ref "R8") (pin "2") (pinfunction "2_2") (pintype "passive"))
      (node (ref "U1") (pin "13") (pinfunction "~{RSTN}_13") (pintype "input"))
    )
    (net (code "41") (name "/~{SS_SEL}") (class "Default")
      (node (ref "U1") (pin "42") (pinfunction "~{SELN}_42") (pintype "input"))
    )
    (net (code "42") (name "AVDD0") (class "Default")
      (node (ref "C20") (pin "1") (pinfunction "1_1") (pintype "passive"))
      (node (ref "TP2") (pin "1") (pinfunction "1_1") (pintype "passive"))
      (node (ref "U1") (pin "14") (pinfunction "AVDD0_14") (pintype "power_in"))
    )
    (net (code "43") (name "AVDD1") (class "Default")
      (node (ref "C19") (pin "1") (pinfunction "1_1") (pintype "passive"))
      (node (ref "TP1") (pin "1") (pinfunction "1_1") (pintype "passive"))
      (node (ref "U1") (pin "47") (pinfunction "AVDD1_47") (pintype "power_in"))
    )
    (net (code "44") (name "DVDD") (class "Default")
      (node (ref "C18") (pin "1") (pinfunction "1_1") (pintype "passive"))
      (node (ref "U1") (pin "37") (pinfunction "DVDD_37") (pintype "power_in"))
    )
    (net (code "45") (name "GND") (class "Default")
      (node (ref "B1") (pin "2") (pinfunction "Feed_GND_2") (pintype "power_in"))
      (node (ref "B1") (pin "5") (pinfunction "GND_5") (pintype "power_in"))
      (node (ref "B2") (pin "2") (pinfunction "Feed_GND_2") (pintype "power_in"))
      (node (ref "B2") (pin "5") (pinfunction "GND_5") (pintype "power_in"))
      (node (ref "B2") (pin "6") (pinfunction "nc_6") (pintype "passive"))
      (node (ref "C1") (pin "1") (pinfunction "1_1") (pintype "passive"))
      (node (ref "C10") (pin "2") (pinfunction "2_2") (pintype "passive"))
      (node (ref "C11") (pin "1") (pinfunction "1_1") (pintype "passive"))
      (node (ref "C13") (pin "2") (pinfunction "2_2") (pintype "passive"))
      (node (ref "C14") (pin "2") (pinfunction "2_2") (pintype "passive"))
      (node (ref "C15") (pin "2") (pinfunction "2_2") (pintype "passive"))
      (node (ref "C16") (pin "2") (pinfunction "2_2") (pintype "passive"))
      (node (ref "C17") (pin "2") (pinfunction "2_2") (pintype "passive"))
      (node (ref "C18") (pin "2") (pinfunction "2_2") (pintype "passive"))
      (node (ref "C19") (pin "2") (pinfunction "2_2") (pintype "passive"))
      (node (ref "C20") (pin "2") (pinfunction "2_2") (pintype "passive"))
      (node (ref "C21") (pin "2") (pinfunction "2_2") (pintype "passive"))
      (node (ref "C22") (pin "2") (pinfunction "2_2") (pintype "passive"))
      (node (ref "C23") (pin "2") (pinfunction "2_2") (pintype "passive"))
      (node (ref "C24") (pin "2") (pinfunction "2_2") (pintype "passive"))
      (node (ref "C4") (pin "2") (pinfunction "2_2") (pintype "passive"))
      (node (ref "C6") (pin "2") (pinfunction "2_2") (pintype "passive"))
      (node (ref "C7") (pin "2") (pinfunction "2_2") (pintype "passive"))
      (node (ref "C9") (pin "2") (pinfunction "2_2") (pintype "passive"))
      (node (ref "FR1") (pin "1") (pinfunction "GND_1") (pintype "passive"))
      (node (ref "P1") (pin "2") (pinfunction "GND_2") (pintype "power_in"))
      (node (ref "P1") (pin "3") (pinfunction "GND_3") (pintype "power_in"))
      (node (ref "Q1") (pin "1") (pinfunction "S2_1") (pintype "passive"))
      (node (ref "Q1") (pin "4") (pinfunction "S1_4") (pintype "passive"))
      (node (ref "R10") (pin "1") (pinfunction "1_1") (pintype "passive"))
      (node (ref "R11") (pin "1") (pinfunction "1_1") (pintype "passive"))
      (node (ref "R13") (pin "1") (pinfunction "1_1") (pintype "passive"))
      (node (ref "R5") (pin "2") (pinfunction "2_2") (pintype "passive"))
      (node (ref "R7") (pin "2") (pinfunction "2_2") (pintype "passive"))
      (node (ref "SMA1") (pin "2") (pinfunction "2_2") (pintype "passive"))
      (node (ref "SMA2") (pin "2") (pinfunction "2_2") (pintype "passive"))
      (node (ref "SW1") (pin "1") (pinfunction "1_1") (pintype "passive"))
      (node (ref "SW1") (pin "2") (pinfunction "2_2") (pintype "passive"))
      (node (ref "TP9") (pin "1") (pinfunction "1_1") (pintype "passive"))
      (node (ref "U1") (pin "10") (pinfunction "AVSS_10") (pintype "power_in"))
      (node (ref "U1") (pin "16") (pinfunction "AVSS_16") (pintype "power_in"))
      (node (ref "U1") (pin "19") (pinfunction "AVSS_19") (pintype "power_in"))
      (node (ref "U1") (pin "20") (pinfunction "DVSS_20") (pintype "power_in"))
      (node (ref "U1") (pin "23") (pinfunction "DVSS_23") (pintype "power_in"))
      (node (ref "U1") (pin "24") (pinfunction "DVSS_24") (pintype "power_in"))
      (node (ref "U1") (pin "3") (pinfunction "AVSS_3") (pintype "power_in"))
      (node (ref "U1") (pin "32") (pinfunction "DVSS_32") (pintype "power_in"))
      (node (ref "U1") (pin "38") (pinfunction "DVSS_38") (pintype "power_in"))
      (node (ref "U1") (pin "45") (pinfunction "AVSS_45") (pintype "power_in"))
      (node (ref "U1") (pin "48") (pinfunction "AVSS_48") (pintype "power_in"))
      (node (ref "U1") (pin "49") (pinfunction "AVSS_49") (pintype "power_in"))
      (node (ref "U1") (pin "6") (pinfunction "AVSS_6") (pintype "power_in"))
      (node (ref "U1") (pin "7") (pinfunction "AVSS_7") (pintype "power_in"))
      (node (ref "U2") (pin "2") (pinfunction "GND_2") (pintype "passive"))
      (node (ref "U2") (pin "5") (pinfunction "WP_5") (pintype "passive"))
      (node (ref "XC1") (pin "2") (pinfunction "GND_2") (pintype "passive"))
    )
    (net (code "46") (name "Net-(B1-unbalanced)") (class "Default")
      (node (ref "B1") (pin "1") (pinfunction "unbalanced_1") (pintype "passive"))
      (node (ref "C3") (pin "1") (pinfunction "1_1") (pintype "passive"))
    )
    (net (code "47") (name "Net-(B2-unbalanced)") (class "Default")
      (node (ref "B2") (pin "1") (pinfunction "unbalanced_1") (pintype "passive"))
      (node (ref "C8") (pin "1") (pinfunction "1_1") (pintype "passive"))
    )
    (net (code "48") (name "Net-(C4-Pad1)") (class "Default")
      (node (ref "C4") (pin "1") (pinfunction "1_1") (pintype "passive"))
      (node (ref "R10") (pin "2") (pinfunction "2_2") (pintype "passive"))
      (node (ref "R4") (pin "2") (pinfunction "2_2") (pintype "passive"))
      (node (ref "SMA2") (pin "1") (pinfunction "1_1") (pintype "passive"))
    )
    (net (code "49") (name "Net-(C7-Pad1)") (class "Default")
      (node (ref "C7") (pin "1") (pinfunction "1_1") (pintype "passive"))
      (node (ref "R11") (pin "2") (pinfunction "2_2") (pintype "passive"))
      (node (ref "R9") (pin "2") (pinfunction "2_2") (pintype "passive"))
      (node (ref "SMA1") (pin "1") (pinfunction "1_1") (pintype "passive"))
    )
    (net (code "50") (name "Net-(C21-Pad1)") (class "Default")
      (node (ref "C21") (pin "1") (pinfunction "1_1") (pintype "passive"))
      (node (ref "C3") (pin "2") (pinfunction "2_2") (pintype "passive"))
      (node (ref "R4") (pin "1") (pinfunction "1_1") (pintype "passive"))
    )
    (net (code "51") (name "Net-(C22-Pad1)") (class "Default")
      (node (ref "C22") (pin "1") (pinfunction "1_1") (pintype "passive"))
      (node (ref "C8") (pin "2") (pinfunction "2_2") (pintype "passive"))
      (node (ref "R9") (pin "1") (pinfunction "1_1") (pintype "passive"))
    )
    (net (code "52") (name "Net-(D1-CATHODE)") (class "Default")
      (node (ref "D1") (pin "1") (pinfunction "CATHODE_1") (pintype "passive"))
      (node (ref "R2") (pin "2") (pinfunction "2_2") (pintype "passive"))
    )
    (net (code "53") (name "Net-(D2-CATHODE)") (class "Default")
      (node (ref "D2") (pin "1") (pinfunction "CATHODE_1") (pintype "passive"))
      (node (ref "R3") (pin "2") (pinfunction "2_2") (pintype "passive"))
    )
    (net (code "54") (name "Net-(P1-SIG)") (class "Default")
      (node (ref "C24") (pin "1") (pinfunction "1_1") (pintype "passive"))
      (node (ref "P1") (pin "1") (pinfunction "SIG_1") (pintype "passive"))
      (node (ref "R12") (pin "1") (pinfunction "1_1") (pintype "passive"))
      (node (ref "TP8") (pin "1") (pinfunction "1_1") (pintype "passive"))
    )
    (net (code "55") (name "Net-(Q1A-D1)") (class "Default")
      (node (ref "Q1") (pin "3") (pinfunction "D1_3") (pintype "passive"))
      (node (ref "R3") (pin "1") (pinfunction "1_1") (pintype "passive"))
    )
    (net (code "56") (name "Net-(Q1B-D2)") (class "Default")
      (node (ref "Q1") (pin "6") (pinfunction "D2_6") (pintype "passive"))
      (node (ref "R2") (pin "1") (pinfunction "1_1") (pintype "passive"))
    )
    (net (code "57") (name "Net-(R8-Pad1)") (class "Default")
      (node (ref "R8") (pin "1") (pinfunction "1_1") (pintype "passive"))
      (node (ref "SW1") (pin "3") (pinfunction "3_3") (pintype "passive"))
      (node (ref "SW1") (pin "4") (pinfunction "4_4") (pintype "passive"))
      (node (ref "TP4") (pin "1") (pinfunction "1_1") (pintype "passive"))
    )
    (net (code "58") (name "Net-(U1-CLKO)") (class "Default")
      (node (ref "R12") (pin "2") (pinfunction "2_2") (pintype "passive"))
      (node (ref "U1") (pin "22") (pinfunction "CLKO_22") (pintype "output"))
    )
    (net (code "59") (name "Net-(U1-TCXO)") (class "Default")
      (node (ref "C10") (pin "1") (pinfunction "1_1") (pintype "passive"))
      (node (ref "C25") (pin "2") (pinfunction "2_2") (pintype "passive"))
      (node (ref "R13") (pin "2") (pinfunction "2_2") (pintype "passive"))
      (node (ref "U1") (pin "17") (pinfunction "TCXO_17") (pintype "input"))
    )
    (net (code "60") (name "Net-(U1-XTAL2)") (class "Default")
      (node (ref "R7") (pin "1") (pinfunction "1_1") (pintype "passive"))
      (node (ref "U1") (pin "18") (pinfunction "XTAL2_18") (pintype "output"))
    )
    (net (code "61") (name "Net-(XC1-OUTPUT)") (class "Default")
      (node (ref "C25") (pin "1") (pinfunction "1_1") (pintype "passive"))
      (node (ref "XC1") (pin "3") (pinfunction "OUTPUT_3") (pintype "passive"))
    )
    (net (code "62") (name "VCC_3V3") (class "Default")
      (node (ref "C13") (pin "1") (pinfunction "1_1") (pintype "passive"))
      (node (ref "C14") (pin "1") (pinfunction "1_1") (pintype "passive"))
      (node (ref "C15") (pin "1") (pinfunction "1_1") (pintype "passive"))
      (node (ref "C16") (pin "1") (pinfunction "1_1") (pintype "passive"))
      (node (ref "C17") (pin "1") (pinfunction "1_1") (pintype "passive"))
      (node (ref "C23") (pin "1") (pinfunction "1_1") (pintype "passive"))
      (node (ref "J1") (pin "1") (pinfunction "1_1") (pintype "passive"))
      (node (ref "R6") (pin "2") (pinfunction "2_2") (pintype "passive"))
      (node (ref "U1") (pin "15") (pinfunction "EVDD_15") (pintype "power_in"))
      (node (ref "U1") (pin "21") (pinfunction "DEVDD_21") (pintype "power_in"))
      (node (ref "U1") (pin "29") (pinfunction "DEVDD_29") (pintype "power_in"))
      (node (ref "U1") (pin "39") (pinfunction "DEVDD_39") (pintype "power_in"))
      (node (ref "U1") (pin "46") (pinfunction "EVDD_46") (pintype "power_in"))
    )
    (net (code "63") (name "VCC_B_3.3V") (class "Default")
      (node (ref "C9") (pin "1") (pinfunction "1_1") (pintype "passive"))
      (node (ref "J1") (pin "2") (pinfunction "2_2") (pintype "passive"))
      (node (ref "L2") (pin "1") (pinfunction "1_1") (pintype "passive"))
      (node (ref "XC1") (pin "4") (pinfunction "VCC_4") (pintype "passive"))
    )
    (net (code "64") (name "VCC_TARGET") (class "Default")
      (node (ref "C1") (pin "2") (pinfunction "2_2") (pintype "passive"))
      (node (ref "C11") (pin "2") (pinfunction "2_2") (pintype "passive"))
      (node (ref "D1") (pin "2") (pinfunction "ANODE_2") (pintype "passive"))
      (node (ref "D2") (pin "2") (pinfunction "ANODE_2") (pintype "passive"))
      (node (ref "L2") (pin "2") (pinfunction "2_2") (pintype "passive"))
      (node (ref "R1") (pin "2") (pinfunction "2_2") (pintype "passive"))
      (node (ref "R101") (pin "2") (pinfunction "2_2") (pintype "passive"))
      (node (ref "R102") (pin "2") (pinfunction "2_2") (pintype "passive"))
      (node (ref "U2") (pin "4") (pinfunction "VCC_4") (pintype "passive"))
    )
    (net (code "65") (name "unconnected-(B1-nc-Pad6)") (class "Default")
      (node (ref "B1") (pin "6") (pinfunction "nc_6") (pintype "passive+no_connect"))
    )
    (net (code "66") (name "unconnected-(XC1-NC-Pad1)") (class "Default")
      (node (ref "XC1") (pin "1") (pinfunction "NC_1") (pintype "passive+no_connect"))
    )
  )
)
